# IN_A.net
KiCad netlist of a schematic drawn in Altium Designer
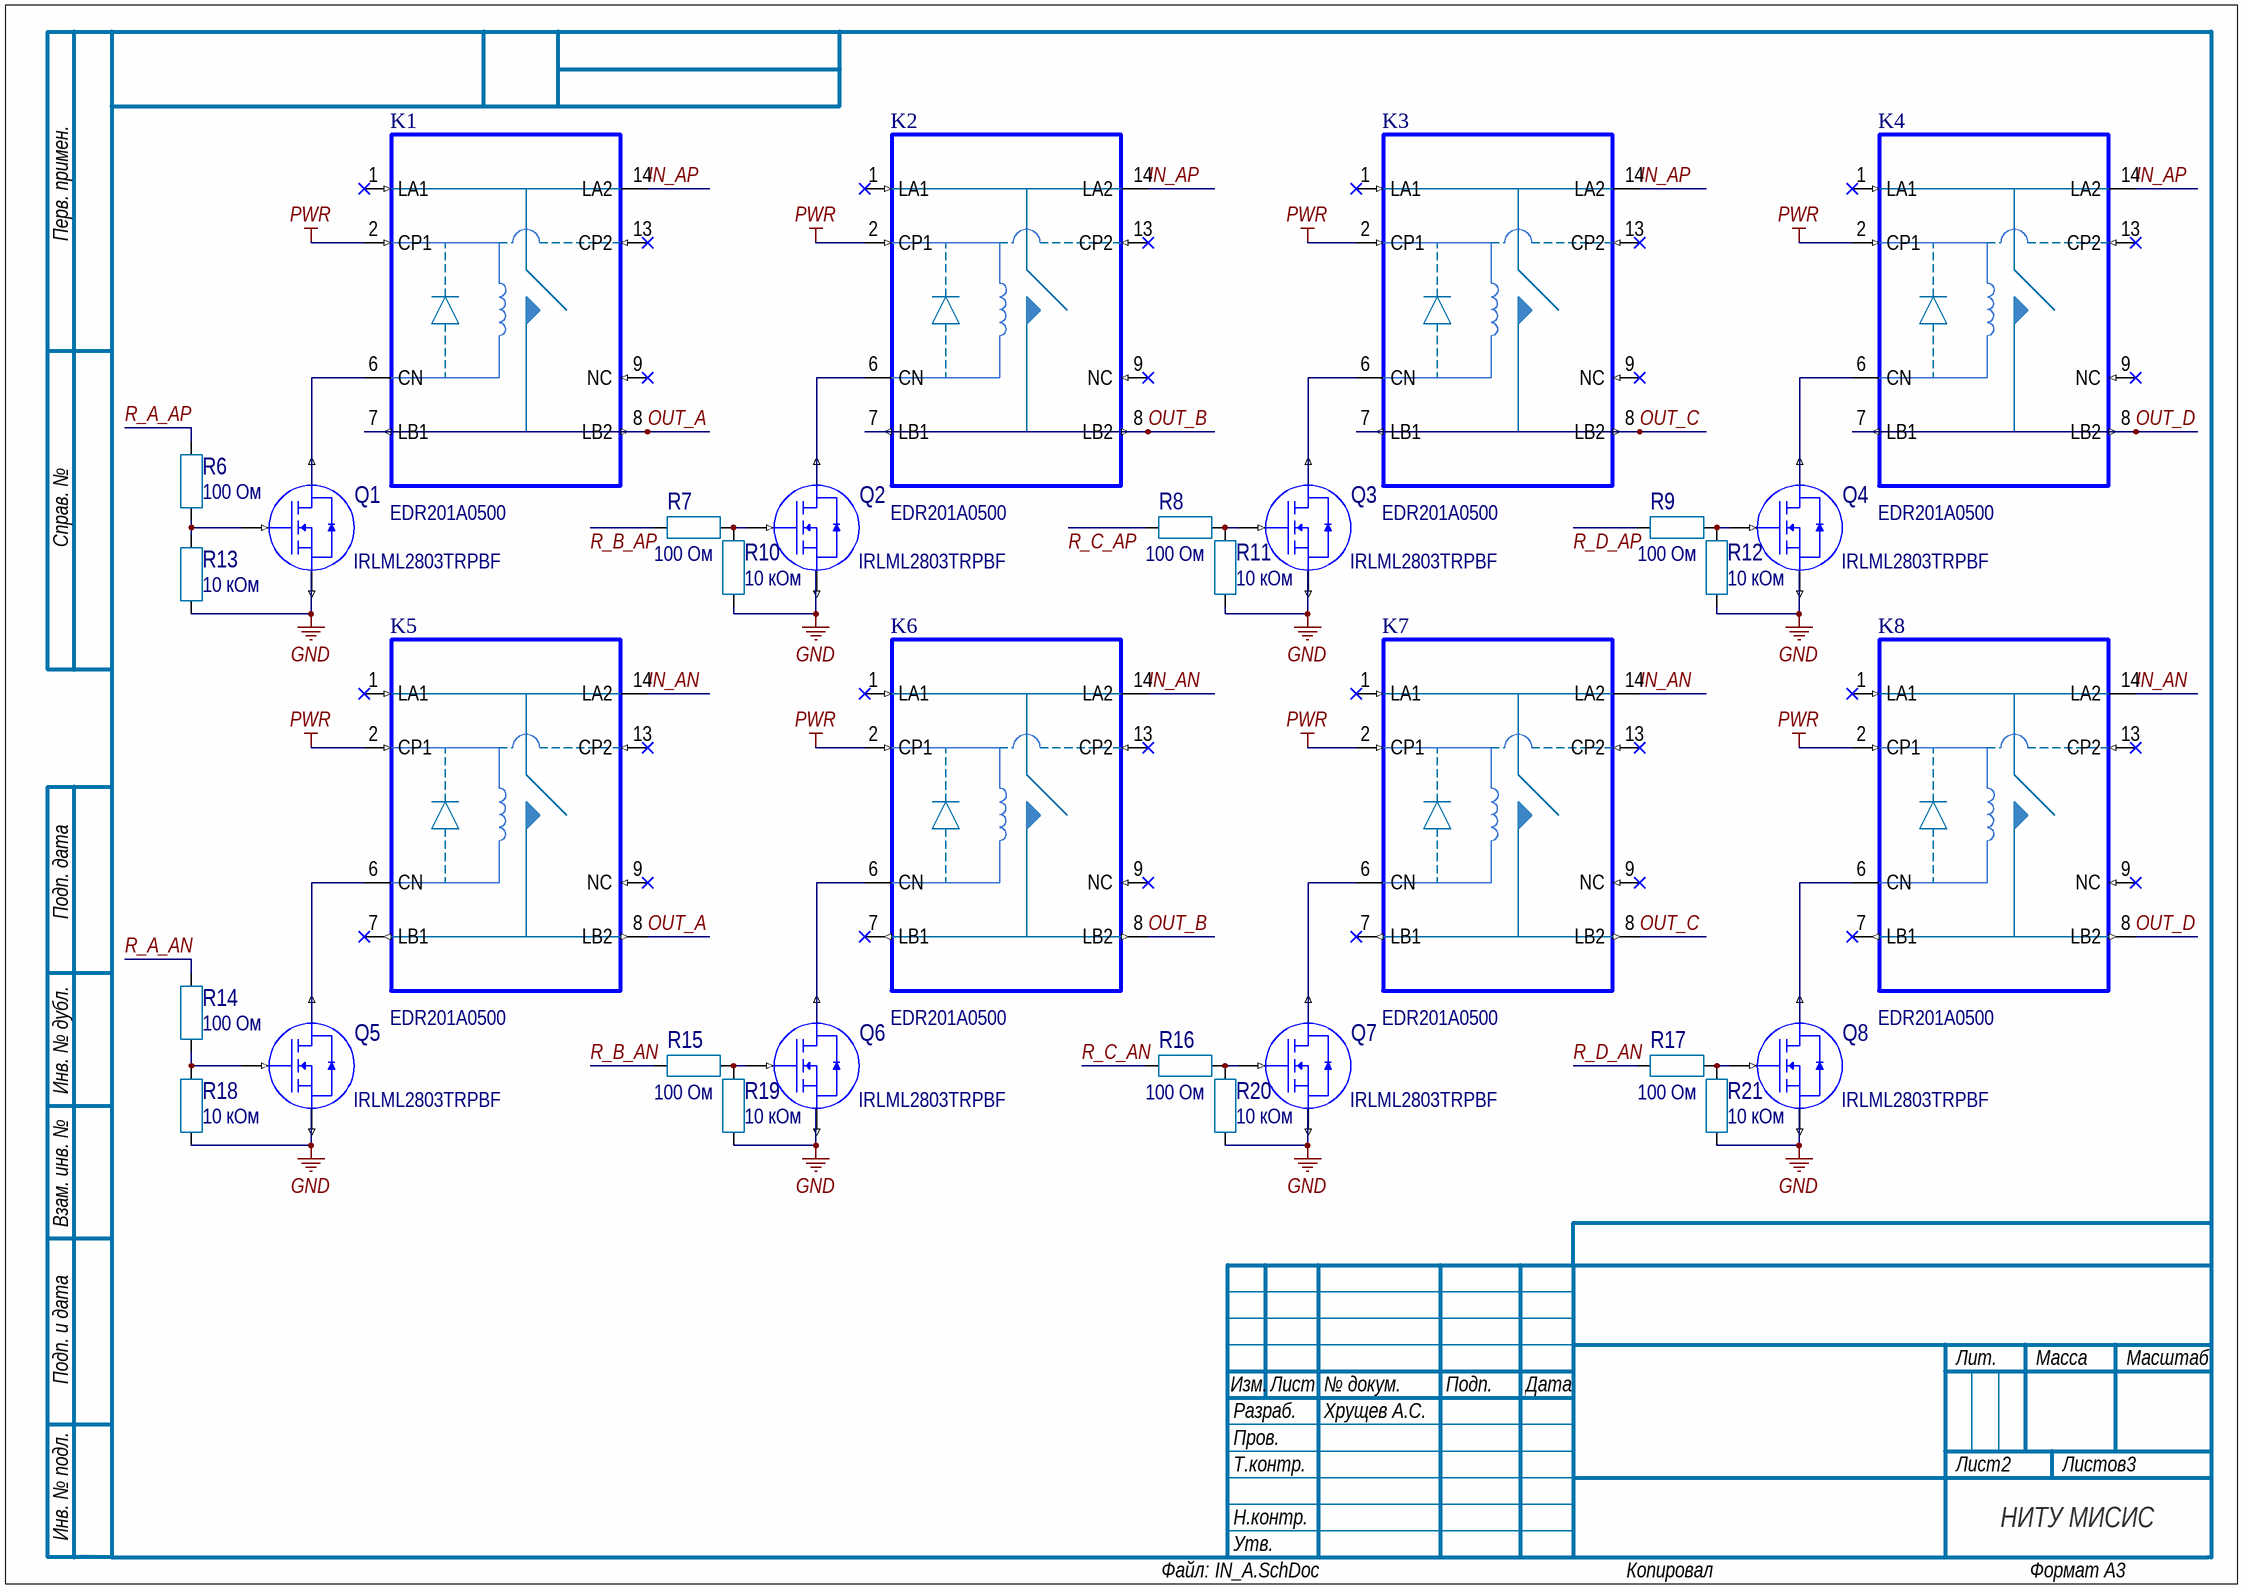
[diagram p0: IN_A.SchDoc]

(export (version "E")
  (design (tool "Eeschema 10.0.6"))
  (components
    (comp (ref "K1")
      (value "EDR201A0500")
      (footprint "DIP14")
      (description "Реле герконовое 5V / 1A,100V")
      (fields (field (name "MF") "Fairchild Semiconductor") (field (name "MP") "MM74HC32N"))
      (libsource (lib "EDR201A0500") (part "EDR201A0500"))
    )
    (comp (ref "K2")
      (value "EDR201A0500")
      (footprint "DIP14")
      (description "Реле герконовое 5V / 1A,100V")
      (fields (field (name "MF") "Fairchild Semiconductor") (field (name "MP") "MM74HC32N"))
      (libsource (lib "EDR201A0500") (part "EDR201A0500"))
    )
    (comp (ref "K3")
      (value "EDR201A0500")
      (footprint "DIP14")
      (description "Реле герконовое 5V / 1A,100V")
      (fields (field (name "MF") "Fairchild Semiconductor") (field (name "MP") "MM74HC32N"))
      (libsource (lib "EDR201A0500") (part "EDR201A0500"))
    )
    (comp (ref "K4")
      (value "EDR201A0500")
      (footprint "DIP14")
      (description "Реле герконовое 5V / 1A,100V")
      (fields (field (name "MF") "Fairchild Semiconductor") (field (name "MP") "MM74HC32N"))
      (libsource (lib "EDR201A0500") (part "EDR201A0500"))
    )
    (comp (ref "K5")
      (value "EDR201A0500")
      (footprint "DIP14")
      (description "Реле герконовое 5V / 1A,100V")
      (fields (field (name "MF") "Fairchild Semiconductor") (field (name "MP") "MM74HC32N"))
      (libsource (lib "EDR201A0500") (part "EDR201A0500"))
    )
    (comp (ref "K6")
      (value "EDR201A0500")
      (footprint "DIP14")
      (description "Реле герконовое 5V / 1A,100V")
      (fields (field (name "MF") "Fairchild Semiconductor") (field (name "MP") "MM74HC32N"))
      (libsource (lib "EDR201A0500") (part "EDR201A0500"))
    )
    (comp (ref "K7")
      (value "EDR201A0500")
      (footprint "DIP14")
      (description "Реле герконовое 5V / 1A,100V")
      (fields (field (name "MF") "Fairchild Semiconductor") (field (name "MP") "MM74HC32N"))
      (libsource (lib "EDR201A0500") (part "EDR201A0500"))
    )
    (comp (ref "K8")
      (value "EDR201A0500")
      (footprint "DIP14")
      (description "Реле герконовое 5V / 1A,100V")
      (fields (field (name "MF") "Fairchild Semiconductor") (field (name "MP") "MM74HC32N"))
      (libsource (lib "EDR201A0500") (part "EDR201A0500"))
    )
    (comp (ref "Q1")
      (value "IRLML2803TRPBF")
      (footprint "SOT23-3")
      (description "N-MOSFET 30V 1.2A SOT23")
      (libsource (lib "symbols") (part "IRLML2803TRPBF"))
    )
    (comp (ref "Q2")
      (value "IRLML2803TRPBF")
      (footprint "SOT23-3")
      (description "N-MOSFET 30V 1.2A SOT23")
      (libsource (lib "symbols") (part "IRLML2803TRPBF"))
    )
    (comp (ref "Q3")
      (value "IRLML2803TRPBF")
      (footprint "SOT23-3")
      (description "N-MOSFET 30V 1.2A SOT23")
      (libsource (lib "symbols") (part "IRLML2803TRPBF"))
    )
    (comp (ref "Q4")
      (value "IRLML2803TRPBF")
      (footprint "SOT23-3")
      (description "N-MOSFET 30V 1.2A SOT23")
      (libsource (lib "symbols") (part "IRLML2803TRPBF"))
    )
    (comp (ref "Q5")
      (value "IRLML2803TRPBF")
      (footprint "SOT23-3")
      (description "N-MOSFET 30V 1.2A SOT23")
      (libsource (lib "symbols") (part "IRLML2803TRPBF"))
    )
    (comp (ref "Q6")
      (value "IRLML2803TRPBF")
      (footprint "SOT23-3")
      (description "N-MOSFET 30V 1.2A SOT23")
      (libsource (lib "symbols") (part "IRLML2803TRPBF"))
    )
    (comp (ref "Q7")
      (value "IRLML2803TRPBF")
      (footprint "SOT23-3")
      (description "N-MOSFET 30V 1.2A SOT23")
      (libsource (lib "symbols") (part "IRLML2803TRPBF"))
    )
    (comp (ref "Q8")
      (value "IRLML2803TRPBF")
      (footprint "SOT23-3")
      (description "N-MOSFET 30V 1.2A SOT23")
      (libsource (lib "symbols") (part "IRLML2803TRPBF"))
    )
    (comp (ref "R6")
      (value "100 Ом")
      (footprint "R0805")
      (description "Резистор 100 Ом")
      (libsource (lib "GOST_2.728_Rezistory&Kondensatory") (part "R1_POSTOYANNYJ"))
    )
    (comp (ref "R7")
      (value "100 Ом")
      (footprint "R0805")
      (description "Резистор 100 Ом")
      (libsource (lib "") (part "R1_POSTOYANNYJ_1"))
    )
    (comp (ref "R8")
      (value "100 Ом")
      (footprint "R0805")
      (description "Резистор 100 Ом")
      (libsource (lib "") (part "R1_POSTOYANNYJ_1"))
    )
    (comp (ref "R9")
      (value "100 Ом")
      (footprint "R0805")
      (description "Резистор 100 Ом")
      (libsource (lib "") (part "R1_POSTOYANNYJ_1"))
    )
    (comp (ref "R10")
      (value "10 кОм")
      (footprint "R0805")
      (description "Резистор 100 Ом")
      (libsource (lib "GOST_2.728_Rezistory&Kondensatory") (part "R1_POSTOYANNYJ"))
    )
    (comp (ref "R11")
      (value "10 кОм")
      (footprint "R0805")
      (description "Резистор 100 Ом")
      (libsource (lib "GOST_2.728_Rezistory&Kondensatory") (part "R1_POSTOYANNYJ"))
    )
    (comp (ref "R12")
      (value "10 кОм")
      (footprint "R0805")
      (description "Резистор 100 Ом")
      (libsource (lib "GOST_2.728_Rezistory&Kondensatory") (part "R1_POSTOYANNYJ"))
    )
    (comp (ref "R13")
      (value "10 кОм")
      (footprint "R0805")
      (description "Резистор 100 Ом")
      (libsource (lib "GOST_2.728_Rezistory&Kondensatory") (part "R1_POSTOYANNYJ"))
    )
    (comp (ref "R14")
      (value "100 Ом")
      (footprint "R0805")
      (description "Резистор 100 Ом")
      (libsource (lib "GOST_2.728_Rezistory&Kondensatory") (part "R1_POSTOYANNYJ"))
    )
    (comp (ref "R15")
      (value "100 Ом")
      (footprint "R0805")
      (description "Резистор 100 Ом")
      (libsource (lib "") (part "R1_POSTOYANNYJ_1"))
    )
    (comp (ref "R16")
      (value "100 Ом")
      (footprint "R0805")
      (description "Резистор 100 Ом")
      (libsource (lib "") (part "R1_POSTOYANNYJ_1"))
    )
    (comp (ref "R17")
      (value "100 Ом")
      (footprint "R0805")
      (description "Резистор 100 Ом")
      (libsource (lib "") (part "R1_POSTOYANNYJ_1"))
    )
    (comp (ref "R18")
      (value "10 кОм")
      (footprint "R0805")
      (description "Резистор 100 Ом")
      (libsource (lib "GOST_2.728_Rezistory&Kondensatory") (part "R1_POSTOYANNYJ"))
    )
    (comp (ref "R19")
      (value "10 кОм")
      (footprint "R0805")
      (description "Резистор 100 Ом")
      (libsource (lib "GOST_2.728_Rezistory&Kondensatory") (part "R1_POSTOYANNYJ"))
    )
    (comp (ref "R20")
      (value "10 кОм")
      (footprint "R0805")
      (description "Резистор 100 Ом")
      (libsource (lib "GOST_2.728_Rezistory&Kondensatory") (part "R1_POSTOYANNYJ"))
    )
    (comp (ref "R21")
      (value "10 кОм")
      (footprint "R0805")
      (description "Резистор 100 Ом")
      (libsource (lib "GOST_2.728_Rezistory&Kondensatory") (part "R1_POSTOYANNYJ"))
    )
  )
  (nets
    (net (code "1") (name "/IN_AN") (class "Default")
      (node (ref "K5") (pin "14") (pinfunction "LA2_14") (pintype "power_in"))
      (node (ref "K6") (pin "14") (pinfunction "LA2_14") (pintype "power_in"))
      (node (ref "K7") (pin "14") (pinfunction "LA2_14") (pintype "power_in"))
      (node (ref "K8") (pin "14") (pinfunction "LA2_14") (pintype "power_in"))
    )
    (net (code "2") (name "/IN_AP") (class "Default")
      (node (ref "K1") (pin "14") (pinfunction "LA2_14") (pintype "power_in"))
      (node (ref "K2") (pin "14") (pinfunction "LA2_14") (pintype "power_in"))
      (node (ref "K3") (pin "14") (pinfunction "LA2_14") (pintype "power_in"))
      (node (ref "K4") (pin "14") (pinfunction "LA2_14") (pintype "power_in"))
    )
    (net (code "3") (name "/OUT_A") (class "Default")
      (node (ref "K1") (pin "7") (pinfunction "LB1_7") (pintype "output"))
      (node (ref "K1") (pin "8") (pinfunction "LB2_8") (pintype "output"))
      (node (ref "K5") (pin "8") (pinfunction "LB2_8") (pintype "output"))
    )
    (net (code "4") (name "/OUT_B") (class "Default")
      (node (ref "K2") (pin "7") (pinfunction "LB1_7") (pintype "output"))
      (node (ref "K2") (pin "8") (pinfunction "LB2_8") (pintype "output"))
      (node (ref "K6") (pin "8") (pinfunction "LB2_8") (pintype "output"))
    )
    (net (code "5") (name "/OUT_C") (class "Default")
      (node (ref "K3") (pin "7") (pinfunction "LB1_7") (pintype "output"))
      (node (ref "K3") (pin "8") (pinfunction "LB2_8") (pintype "output"))
      (node (ref "K7") (pin "8") (pinfunction "LB2_8") (pintype "output"))
    )
    (net (code "6") (name "/OUT_D") (class "Default")
      (node (ref "K4") (pin "7") (pinfunction "LB1_7") (pintype "output"))
      (node (ref "K4") (pin "8") (pinfunction "LB2_8") (pintype "output"))
      (node (ref "K8") (pin "8") (pinfunction "LB2_8") (pintype "output"))
    )
    (net (code "7") (name "/R_A_AN") (class "Default")
      (node (ref "R14") (pin "2") (pinfunction "2_2") (pintype "passive"))
    )
    (net (code "8") (name "/R_A_AP") (class "Default")
      (node (ref "R6") (pin "2") (pinfunction "2_2") (pintype "passive"))
    )
    (net (code "9") (name "/R_B_AN") (class "Default")
      (node (ref "R15") (pin "1") (pinfunction "1_1") (pintype "passive"))
    )
    (net (code "10") (name "/R_B_AP") (class "Default")
      (node (ref "R7") (pin "1") (pinfunction "1_1") (pintype "passive"))
    )
    (net (code "11") (name "/R_C_AN") (class "Default")
      (node (ref "R16") (pin "1") (pinfunction "1_1") (pintype "passive"))
    )
    (net (code "12") (name "/R_C_AP") (class "Default")
      (node (ref "R8") (pin "1") (pinfunction "1_1") (pintype "passive"))
    )
    (net (code "13") (name "/R_D_AN") (class "Default")
      (node (ref "R17") (pin "1") (pinfunction "1_1") (pintype "passive"))
    )
    (net (code "14") (name "/R_D_AP") (class "Default")
      (node (ref "R9") (pin "1") (pinfunction "1_1") (pintype "passive"))
    )
    (net (code "15") (name "GND") (class "Default")
      (node (ref "Q1") (pin "2") (pinfunction "S_2") (pintype "input"))
      (node (ref "Q2") (pin "2") (pinfunction "S_2") (pintype "input"))
      (node (ref "Q3") (pin "2") (pinfunction "S_2") (pintype "input"))
      (node (ref "Q4") (pin "2") (pinfunction "S_2") (pintype "input"))
      (node (ref "Q5") (pin "2") (pinfunction "S_2") (pintype "input"))
      (node (ref "Q6") (pin "2") (pinfunction "S_2") (pintype "input"))
      (node (ref "Q7") (pin "2") (pinfunction "S_2") (pintype "input"))
      (node (ref "Q8") (pin "2") (pinfunction "S_2") (pintype "input"))
      (node (ref "R10") (pin "1") (pinfunction "1_1") (pintype "passive"))
      (node (ref "R11") (pin "1") (pinfunction "1_1") (pintype "passive"))
      (node (ref "R12") (pin "1") (pinfunction "1_1") (pintype "passive"))
      (node (ref "R13") (pin "1") (pinfunction "1_1") (pintype "passive"))
      (node (ref "R18") (pin "1") (pinfunction "1_1") (pintype "passive"))
      (node (ref "R19") (pin "1") (pinfunction "1_1") (pintype "passive"))
      (node (ref "R20") (pin "1") (pinfunction "1_1") (pintype "passive"))
      (node (ref "R21") (pin "1") (pinfunction "1_1") (pintype "passive"))
    )
    (net (code "16") (name "Net-(K1-CN)") (class "Default")
      (node (ref "K1") (pin "6") (pinfunction "CN_6") (pintype "passive"))
      (node (ref "Q1") (pin "3") (pinfunction "D_3") (pintype "input"))
    )
    (net (code "17") (name "Net-(K2-CN)") (class "Default")
      (node (ref "K2") (pin "6") (pinfunction "CN_6") (pintype "passive"))
      (node (ref "Q2") (pin "3") (pinfunction "D_3") (pintype "input"))
    )
    (net (code "18") (name "Net-(K3-CN)") (class "Default")
      (node (ref "K3") (pin "6") (pinfunction "CN_6") (pintype "passive"))
      (node (ref "Q3") (pin "3") (pinfunction "D_3") (pintype "input"))
    )
    (net (code "19") (name "Net-(K4-CN)") (class "Default")
      (node (ref "K4") (pin "6") (pinfunction "CN_6") (pintype "passive"))
      (node (ref "Q4") (pin "3") (pinfunction "D_3") (pintype "input"))
    )
    (net (code "20") (name "Net-(K5-CN)") (class "Default")
      (node (ref "K5") (pin "6") (pinfunction "CN_6") (pintype "passive"))
      (node (ref "Q5") (pin "3") (pinfunction "D_3") (pintype "input"))
    )
    (net (code "21") (name "Net-(K6-CN)") (class "Default")
      (node (ref "K6") (pin "6") (pinfunction "CN_6") (pintype "passive"))
      (node (ref "Q6") (pin "3") (pinfunction "D_3") (pintype "input"))
    )
    (net (code "22") (name "Net-(K7-CN)") (class "Default")
      (node (ref "K7") (pin "6") (pinfunction "CN_6") (pintype "passive"))
      (node (ref "Q7") (pin "3") (pinfunction "D_3") (pintype "input"))
    )
    (net (code "23") (name "Net-(K8-CN)") (class "Default")
      (node (ref "K8") (pin "6") (pinfunction "CN_6") (pintype "passive"))
      (node (ref "Q8") (pin "3") (pinfunction "D_3") (pintype "input"))
    )
    (net (code "24") (name "Net-(Q1-G)") (class "Default")
      (node (ref "Q1") (pin "1") (pinfunction "G_1") (pintype "input"))
      (node (ref "R13") (pin "2") (pinfunction "2_2") (pintype "passive"))
      (node (ref "R6") (pin "1") (pinfunction "1_1") (pintype "passive"))
    )
    (net (code "25") (name "Net-(Q2-G)") (class "Default")
      (node (ref "Q2") (pin "1") (pinfunction "G_1") (pintype "input"))
      (node (ref "R10") (pin "2") (pinfunction "2_2") (pintype "passive"))
      (node (ref "R7") (pin "2") (pinfunction "2_2") (pintype "passive"))
    )
    (net (code "26") (name "Net-(Q3-G)") (class "Default")
      (node (ref "Q3") (pin "1") (pinfunction "G_1") (pintype "input"))
      (node (ref "R11") (pin "2") (pinfunction "2_2") (pintype "passive"))
      (node (ref "R8") (pin "2") (pinfunction "2_2") (pintype "passive"))
    )
    (net (code "27") (name "Net-(Q4-G)") (class "Default")
      (node (ref "Q4") (pin "1") (pinfunction "G_1") (pintype "input"))
      (node (ref "R12") (pin "2") (pinfunction "2_2") (pintype "passive"))
      (node (ref "R9") (pin "2") (pinfunction "2_2") (pintype "passive"))
    )
    (net (code "28") (name "Net-(Q5-G)") (class "Default")
      (node (ref "Q5") (pin "1") (pinfunction "G_1") (pintype "input"))
      (node (ref "R14") (pin "1") (pinfunction "1_1") (pintype "passive"))
      (node (ref "R18") (pin "2") (pinfunction "2_2") (pintype "passive"))
    )
    (net (code "29") (name "Net-(Q6-G)") (class "Default")
      (node (ref "Q6") (pin "1") (pinfunction "G_1") (pintype "input"))
      (node (ref "R15") (pin "2") (pinfunction "2_2") (pintype "passive"))
      (node (ref "R19") (pin "2") (pinfunction "2_2") (pintype "passive"))
    )
    (net (code "30") (name "Net-(Q7-G)") (class "Default")
      (node (ref "Q7") (pin "1") (pinfunction "G_1") (pintype "input"))
      (node (ref "R16") (pin "2") (pinfunction "2_2") (pintype "passive"))
      (node (ref "R20") (pin "2") (pinfunction "2_2") (pintype "passive"))
    )
    (net (code "31") (name "Net-(Q8-G)") (class "Default")
      (node (ref "Q8") (pin "1") (pinfunction "G_1") (pintype "input"))
      (node (ref "R17") (pin "2") (pinfunction "2_2") (pintype "passive"))
      (node (ref "R21") (pin "2") (pinfunction "2_2") (pintype "passive"))
    )
    (net (code "32") (name "PWR") (class "Default")
      (node (ref "K1") (pin "2") (pinfunction "CP1_2") (pintype "input"))
      (node (ref "K2") (pin "2") (pinfunction "CP1_2") (pintype "input"))
      (node (ref "K3") (pin "2") (pinfunction "CP1_2") (pintype "input"))
      (node (ref "K4") (pin "2") (pinfunction "CP1_2") (pintype "input"))
      (node (ref "K5") (pin "2") (pinfunction "CP1_2") (pintype "input"))
      (node (ref "K6") (pin "2") (pinfunction "CP1_2") (pintype "input"))
      (node (ref "K7") (pin "2") (pinfunction "CP1_2") (pintype "input"))
      (node (ref "K8") (pin "2") (pinfunction "CP1_2") (pintype "input"))
    )
    (net (code "33") (name "unconnected-(K1-CP2-Pad13)") (class "Default")
      (node (ref "K1") (pin "13") (pinfunction "CP2_13") (pintype "input+no_connect"))
    )
    (net (code "34") (name "unconnected-(K1-LA1-Pad1)") (class "Default")
      (node (ref "K1") (pin "1") (pinfunction "LA1_1") (pintype "input+no_connect"))
    )
    (net (code "35") (name "unconnected-(K1-NC-Pad9)") (class "Default")
      (node (ref "K1") (pin "9") (pinfunction "NC_9") (pintype "input+no_connect"))
    )
    (net (code "36") (name "unconnected-(K2-CP2-Pad13)") (class "Default")
      (node (ref "K2") (pin "13") (pinfunction "CP2_13") (pintype "input+no_connect"))
    )
    (net (code "37") (name "unconnected-(K2-LA1-Pad1)") (class "Default")
      (node (ref "K2") (pin "1") (pinfunction "LA1_1") (pintype "input+no_connect"))
    )
    (net (code "38") (name "unconnected-(K2-NC-Pad9)") (class "Default")
      (node (ref "K2") (pin "9") (pinfunction "NC_9") (pintype "input+no_connect"))
    )
    (net (code "39") (name "unconnected-(K3-CP2-Pad13)") (class "Default")
      (node (ref "K3") (pin "13") (pinfunction "CP2_13") (pintype "input+no_connect"))
    )
    (net (code "40") (name "unconnected-(K3-LA1-Pad1)") (class "Default")
      (node (ref "K3") (pin "1") (pinfunction "LA1_1") (pintype "input+no_connect"))
    )
    (net (code "41") (name "unconnected-(K3-NC-Pad9)") (class "Default")
      (node (ref "K3") (pin "9") (pinfunction "NC_9") (pintype "input+no_connect"))
    )
    (net (code "42") (name "unconnected-(K4-CP2-Pad13)") (class "Default")
      (node (ref "K4") (pin "13") (pinfunction "CP2_13") (pintype "input+no_connect"))
    )
    (net (code "43") (name "unconnected-(K4-LA1-Pad1)") (class "Default")
      (node (ref "K4") (pin "1") (pinfunction "LA1_1") (pintype "input+no_connect"))
    )
    (net (code "44") (name "unconnected-(K4-NC-Pad9)") (class "Default")
      (node (ref "K4") (pin "9") (pinfunction "NC_9") (pintype "input+no_connect"))
    )
    (net (code "45") (name "unconnected-(K5-CP2-Pad13)") (class "Default")
      (node (ref "K5") (pin "13") (pinfunction "CP2_13") (pintype "input+no_connect"))
    )
    (net (code "46") (name "unconnected-(K5-LA1-Pad1)") (class "Default")
      (node (ref "K5") (pin "1") (pinfunction "LA1_1") (pintype "input+no_connect"))
    )
    (net (code "47") (name "unconnected-(K5-LB1-Pad7)") (class "Default")
      (node (ref "K5") (pin "7") (pinfunction "LB1_7") (pintype "output+no_connect"))
    )
    (net (code "48") (name "unconnected-(K5-NC-Pad9)") (class "Default")
      (node (ref "K5") (pin "9") (pinfunction "NC_9") (pintype "input+no_connect"))
    )
    (net (code "49") (name "unconnected-(K6-CP2-Pad13)") (class "Default")
      (node (ref "K6") (pin "13") (pinfunction "CP2_13") (pintype "input+no_connect"))
    )
    (net (code "50") (name "unconnected-(K6-LA1-Pad1)") (class "Default")
      (node (ref "K6") (pin "1") (pinfunction "LA1_1") (pintype "input+no_connect"))
    )
    (net (code "51") (name "unconnected-(K6-LB1-Pad7)") (class "Default")
      (node (ref "K6") (pin "7") (pinfunction "LB1_7") (pintype "output+no_connect"))
    )
    (net (code "52") (name "unconnected-(K6-NC-Pad9)") (class "Default")
      (node (ref "K6") (pin "9") (pinfunction "NC_9") (pintype "input+no_connect"))
    )
    (net (code "53") (name "unconnected-(K7-CP2-Pad13)") (class "Default")
      (node (ref "K7") (pin "13") (pinfunction "CP2_13") (pintype "input+no_connect"))
    )
    (net (code "54") (name "unconnected-(K7-LA1-Pad1)") (class "Default")
      (node (ref "K7") (pin "1") (pinfunction "LA1_1") (pintype "input+no_connect"))
    )
    (net (code "55") (name "unconnected-(K7-LB1-Pad7)") (class "Default")
      (node (ref "K7") (pin "7") (pinfunction "LB1_7") (pintype "output+no_connect"))
    )
    (net (code "56") (name "unconnected-(K7-NC-Pad9)") (class "Default")
      (node (ref "K7") (pin "9") (pinfunction "NC_9") (pintype "input+no_connect"))
    )
    (net (code "57") (name "unconnected-(K8-CP2-Pad13)") (class "Default")
      (node (ref "K8") (pin "13") (pinfunction "CP2_13") (pintype "input+no_connect"))
    )
    (net (code "58") (name "unconnected-(K8-LA1-Pad1)") (class "Default")
      (node (ref "K8") (pin "1") (pinfunction "LA1_1") (pintype "input+no_connect"))
    )
    (net (code "59") (name "unconnected-(K8-LB1-Pad7)") (class "Default")
      (node (ref "K8") (pin "7") (pinfunction "LB1_7") (pintype "output+no_connect"))
    )
    (net (code "60") (name "unconnected-(K8-NC-Pad9)") (class "Default")
      (node (ref "K8") (pin "9") (pinfunction "NC_9") (pintype "input+no_connect"))
    )
  )
)
